# KitchenTimer.net
KiCad netlist of a schematic drawn in EAGLE
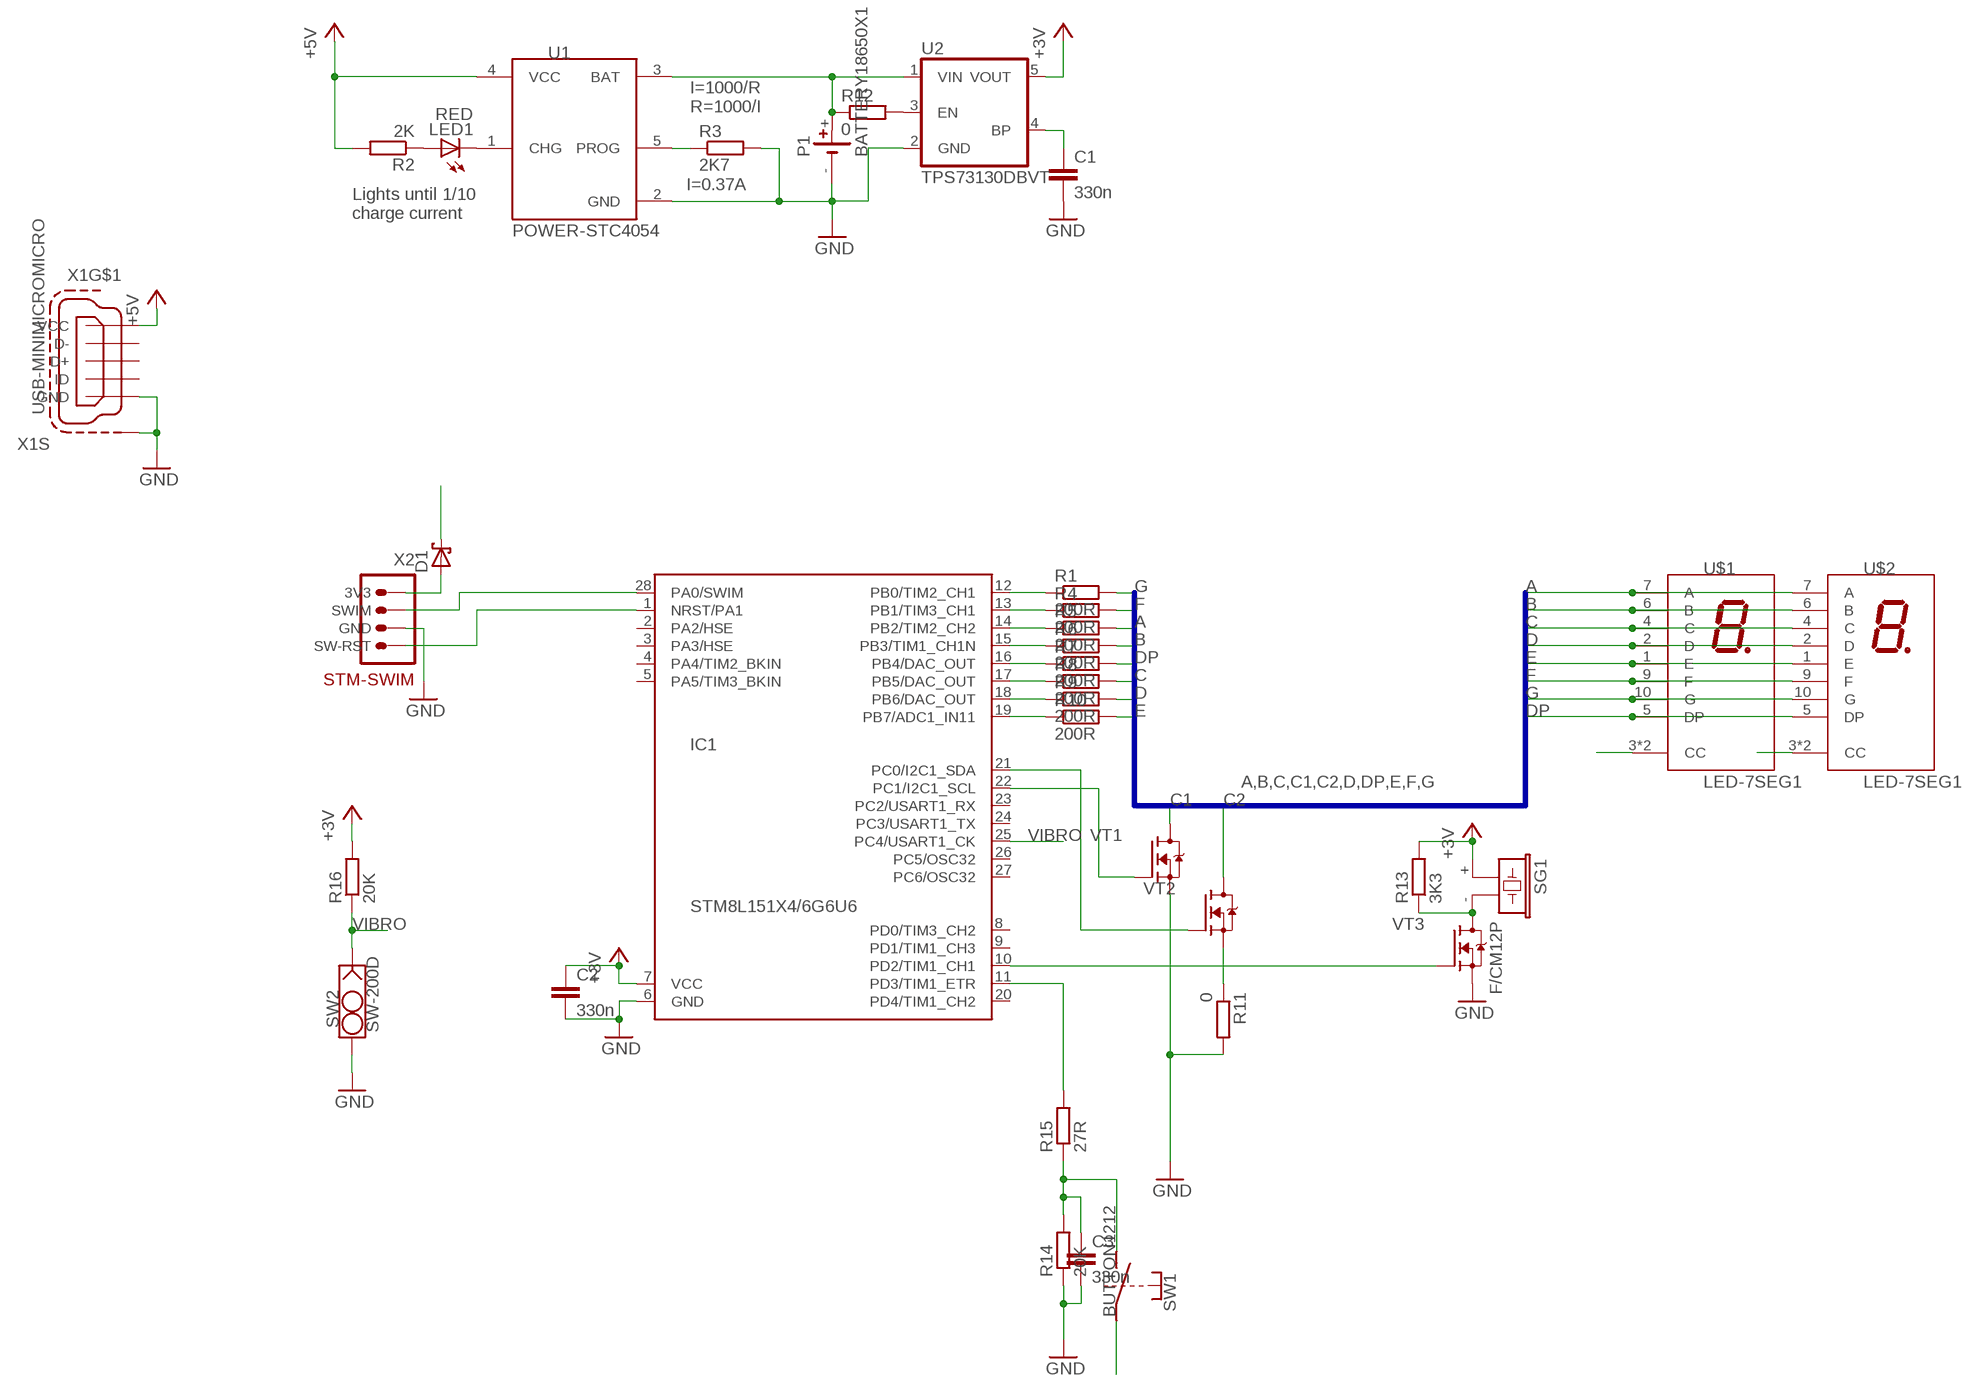
[diagram p0: schematic, sheet 1]

(export (version "E")
  (design (tool "Eeschema 10.0.6"))
  (components
    (comp (ref "C1")
      (value "330n")
      (footprint "eagle-import:CAP1206")
      (libsource (lib "eagle-import") (part "CAP_1206"))
    )
    (comp (ref "C2")
      (value "330n")
      (footprint "eagle-import:CAP1206")
      (libsource (lib "eagle-import") (part "CAP_1206"))
    )
    (comp (ref "C3")
      (value "330n")
      (footprint "eagle-import:CAP1206")
      (libsource (lib "eagle-import") (part "CAP_1206"))
    )
    (comp (ref "D1")
      (value "DIODE-SH_SOD523")
      (footprint "eagle-import:SODFL1608X65")
      (libsource (lib "eagle-import") (part "DIODE-SH_SOD523"))
    )
    (comp (ref "IC1")
      (value "STM8L151X4/6G6U6")
      (footprint "eagle-import:QFN28")
      (libsource (lib "eagle-import") (part "STM8L151X4/6G6U6"))
    )
    (comp (ref "LED1")
      (value "RED")
      (footprint "eagle-import:LED1206")
      (libsource (lib "eagle-import") (part "LED_1206"))
    )
    (comp (ref "P1")
      (value "BATTERY18650X1")
      (footprint "eagle-import:18650X1_HOLDER")
      (libsource (lib "eagle-import") (part "BATTERY18650X1"))
    )
    (comp (ref "R1")
      (value "200R")
      (footprint "eagle-import:RESC2012X50")
      (libsource (lib "eagle-import") (part "R_R0805"))
    )
    (comp (ref "R2")
      (value "2K")
      (footprint "eagle-import:RESC2012X50")
      (libsource (lib "eagle-import") (part "R_R0805"))
    )
    (comp (ref "R3")
      (value "2K7")
      (footprint "eagle-import:RESC2012X50")
      (libsource (lib "eagle-import") (part "R_R0805"))
    )
    (comp (ref "R4")
      (value "200R")
      (footprint "eagle-import:RESC2012X50")
      (libsource (lib "eagle-import") (part "R_R0805"))
    )
    (comp (ref "R5")
      (value "200R")
      (footprint "eagle-import:RESC2012X50")
      (libsource (lib "eagle-import") (part "R_R0805"))
    )
    (comp (ref "R6")
      (value "200R")
      (footprint "eagle-import:RESC2012X50")
      (libsource (lib "eagle-import") (part "R_R0805"))
    )
    (comp (ref "R7")
      (value "200R")
      (footprint "eagle-import:RESC2012X50")
      (libsource (lib "eagle-import") (part "R_R0805"))
    )
    (comp (ref "R8")
      (value "200R")
      (footprint "eagle-import:RESC2012X50")
      (libsource (lib "eagle-import") (part "R_R0805"))
    )
    (comp (ref "R9")
      (value "200R")
      (footprint "eagle-import:RESC2012X50")
      (libsource (lib "eagle-import") (part "R_R0805"))
    )
    (comp (ref "R10")
      (value "200R")
      (footprint "eagle-import:RESC2012X50")
      (libsource (lib "eagle-import") (part "R_R0805"))
    )
    (comp (ref "R11")
      (value "0")
      (footprint "eagle-import:RESC2012X50")
      (libsource (lib "eagle-import") (part "R_R0805"))
    )
    (comp (ref "R12")
      (value "0")
      (footprint "eagle-import:RESC2012X50")
      (libsource (lib "eagle-import") (part "R_R0805"))
    )
    (comp (ref "R13")
      (value "3K3")
      (footprint "eagle-import:RESC3216X60")
      (libsource (lib "eagle-import") (part "R_R1206"))
    )
    (comp (ref "R14")
      (value "20K")
      (footprint "eagle-import:RESC3216X60")
      (libsource (lib "eagle-import") (part "R_R1206"))
    )
    (comp (ref "R15")
      (value "27R")
      (footprint "eagle-import:RESC3216X60")
      (libsource (lib "eagle-import") (part "R_R1206"))
    )
    (comp (ref "R16")
      (value "20K")
      (footprint "eagle-import:RESC3216X60")
      (libsource (lib "eagle-import") (part "R_R1206"))
    )
    (comp (ref "SG1")
      (value "F/CM12P")
      (footprint "eagle-import:F_CM12P")
      (libsource (lib "eagle-import") (part "F/CM12P"))
    )
    (comp (ref "SW1")
      (value "BUTTON1212")
      (footprint "eagle-import:B3F-40XX")
      (libsource (lib "eagle-import") (part "BUTTON1212"))
    )
    (comp (ref "SW2")
      (value "SW-200D")
      (footprint "eagle-import:SW-200D")
      (libsource (lib "eagle-import") (part "SW-200D"))
    )
    (comp (ref "U$1")
      (value "LED-7SEG1")
      (footprint "eagle-import:LED-7SEG1")
      (libsource (lib "eagle-import") (part "LED-7SEG1"))
    )
    (comp (ref "U$2")
      (value "LED-7SEG1")
      (footprint "eagle-import:LED-7SEG1")
      (libsource (lib "eagle-import") (part "LED-7SEG1"))
    )
    (comp (ref "U1")
      (value "POWER-STC4054")
      (footprint "eagle-import:SOT95P280X145-5")
      (libsource (lib "eagle-import") (part "POWER-STC4054"))
    )
    (comp (ref "U2")
      (value "TPS73130DBVT")
      (footprint "eagle-import:SOT95P280X145-5")
      (libsource (lib "eagle-import") (part "VREG-LD2985"))
    )
    (comp (ref "VT1")
      (value "FET-NSOT-23")
      (footprint "eagle-import:SOT95P240X115-3")
      (libsource (lib "eagle-import") (part "FET-NSOT-23"))
    )
    (comp (ref "VT2")
      (value "FET-NSOT-23")
      (footprint "eagle-import:SOT95P240X115-3")
      (libsource (lib "eagle-import") (part "FET-NSOT-23"))
    )
    (comp (ref "VT3")
      (value "FET-NSOT-23")
      (footprint "eagle-import:SOT95P240X115-3")
      (libsource (lib "eagle-import") (part "FET-NSOT-23"))
    )
    (comp (ref "X1")
      (value "USB-MINIMICROMICRO")
      (footprint "eagle-import:USB-B-MICRO-SMD")
      (libsource (lib "eagle-import") (part "USB-MINIMICROMICRO"))
    )
    (comp (ref "X2")
      (value "STM-SWIMPOGOPADS")
      (footprint "eagle-import:SWIM-PADS-1.27")
      (libsource (lib "eagle-import") (part "STM-SWIMPOGOPADS"))
    )
  )
  (nets
    (net (code "1") (name "+3V") (class "Default")
      (node (ref "C2") (pin "1") (pinfunction "1_1") (pintype "passive"))
      (node (ref "D1") (pin "1") (pinfunction "C_1") (pintype "passive"))
      (node (ref "IC1") (pin "7") (pinfunction "VCC_7") (pintype "power_in"))
      (node (ref "R13") (pin "2") (pinfunction "2_2") (pintype "passive"))
      (node (ref "R16") (pin "2") (pinfunction "2_2") (pintype "passive"))
      (node (ref "SG1") (pin "+") (pinfunction "1_+") (pintype "passive"))
      (node (ref "SW1") (pin "1") (pinfunction "1_1") (pintype "passive"))
      (node (ref "SW1") (pin "2") (pinfunction "1_2") (pintype "passive"))
      (node (ref "U2") (pin "5") (pinfunction "VOUT_5") (pintype "passive"))
    )
    (net (code "2") (name "+5V") (class "Default")
      (node (ref "R2") (pin "2") (pinfunction "2_2") (pintype "passive"))
      (node (ref "U1") (pin "4") (pinfunction "VCC_4") (pintype "power_in"))
      (node (ref "X1") (pin "VBUS") (pinfunction "VCC_VBUS") (pintype "passive"))
    )
    (net (code "3") (name "/A") (class "Default")
      (node (ref "R5") (pin "2") (pinfunction "2_2") (pintype "passive"))
      (node (ref "U$1") (pin "7") (pinfunction "A_7") (pintype "bidirectional"))
      (node (ref "U$2") (pin "7") (pinfunction "A_7") (pintype "bidirectional"))
    )
    (net (code "4") (name "/B") (class "Default")
      (node (ref "R6") (pin "2") (pinfunction "2_2") (pintype "passive"))
      (node (ref "U$1") (pin "6") (pinfunction "B_6") (pintype "bidirectional"))
      (node (ref "U$2") (pin "6") (pinfunction "B_6") (pintype "bidirectional"))
    )
    (net (code "5") (name "/C") (class "Default")
      (node (ref "R8") (pin "2") (pinfunction "2_2") (pintype "passive"))
      (node (ref "U$1") (pin "4") (pinfunction "C_4") (pintype "bidirectional"))
      (node (ref "U$2") (pin "4") (pinfunction "C_4") (pintype "bidirectional"))
    )
    (net (code "6") (name "/C1") (class "Default")
      (node (ref "U$1") (pin "3") (pinfunction "CC_3") (pintype "bidirectional"))
      (node (ref "U$1") (pin "8") (pinfunction "CC_8") (pintype "bidirectional"))
      (node (ref "VT1") (pin "3") (pinfunction "D_3") (pintype "passive"))
    )
    (net (code "7") (name "/C2") (class "Default")
      (node (ref "U$2") (pin "3") (pinfunction "CC_3") (pintype "bidirectional"))
      (node (ref "U$2") (pin "8") (pinfunction "CC_8") (pintype "bidirectional"))
      (node (ref "VT2") (pin "3") (pinfunction "D_3") (pintype "passive"))
    )
    (net (code "8") (name "/D") (class "Default")
      (node (ref "R9") (pin "2") (pinfunction "2_2") (pintype "passive"))
      (node (ref "U$1") (pin "2") (pinfunction "D_2") (pintype "bidirectional"))
      (node (ref "U$2") (pin "2") (pinfunction "D_2") (pintype "bidirectional"))
    )
    (net (code "9") (name "/DP") (class "Default")
      (node (ref "R7") (pin "2") (pinfunction "2_2") (pintype "passive"))
      (node (ref "U$1") (pin "5") (pinfunction "DP_5") (pintype "bidirectional"))
      (node (ref "U$2") (pin "5") (pinfunction "DP_5") (pintype "bidirectional"))
    )
    (net (code "10") (name "/E") (class "Default")
      (node (ref "R10") (pin "2") (pinfunction "2_2") (pintype "passive"))
      (node (ref "U$1") (pin "1") (pinfunction "E_1") (pintype "bidirectional"))
      (node (ref "U$2") (pin "1") (pinfunction "E_1") (pintype "bidirectional"))
    )
    (net (code "11") (name "/F") (class "Default")
      (node (ref "R4") (pin "2") (pinfunction "2_2") (pintype "passive"))
      (node (ref "U$1") (pin "9") (pinfunction "F_9") (pintype "bidirectional"))
      (node (ref "U$2") (pin "9") (pinfunction "F_9") (pintype "bidirectional"))
    )
    (net (code "12") (name "/G") (class "Default")
      (node (ref "R1") (pin "2") (pinfunction "2_2") (pintype "passive"))
      (node (ref "U$1") (pin "10") (pinfunction "G_10") (pintype "bidirectional"))
      (node (ref "U$2") (pin "10") (pinfunction "G_10") (pintype "bidirectional"))
    )
    (net (code "13") (name "/VIBRO") (class "Default")
      (node (ref "IC1") (pin "25") (pinfunction "PC4/USART1_CK_25") (pintype "bidirectional"))
      (node (ref "R16") (pin "1") (pinfunction "1_1") (pintype "passive"))
      (node (ref "SW2") (pin "G") (pinfunction "G_G") (pintype "bidirectional"))
    )
    (net (code "14") (name "GND") (class "Default")
      (node (ref "C1") (pin "2") (pinfunction "2_2") (pintype "passive"))
      (node (ref "C2") (pin "2") (pinfunction "2_2") (pintype "passive"))
      (node (ref "C3") (pin "2") (pinfunction "2_2") (pintype "passive"))
      (node (ref "IC1") (pin "6") (pinfunction "GND_6") (pintype "power_in"))
      (node (ref "P1") (pin "-") (pinfunction "-_-") (pintype "passive"))
      (node (ref "R11") (pin "2") (pinfunction "2_2") (pintype "passive"))
      (node (ref "R14") (pin "1") (pinfunction "1_1") (pintype "passive"))
      (node (ref "R3") (pin "2") (pinfunction "2_2") (pintype "passive"))
      (node (ref "SW2") (pin "S") (pinfunction "S_S") (pintype "bidirectional"))
      (node (ref "U1") (pin "2") (pinfunction "GND_2") (pintype "power_in"))
      (node (ref "U2") (pin "2") (pinfunction "GND_2") (pintype "passive"))
      (node (ref "VT1") (pin "2") (pinfunction "S_2") (pintype "passive"))
      (node (ref "VT3") (pin "2") (pinfunction "S_2") (pintype "passive"))
      (node (ref "X1") (pin "GND") (pinfunction "GND_GND") (pintype "passive"))
      (node (ref "X1") (pin "SHIELD1") (pinfunction "S1_SHIELD1") (pintype "passive"))
      (node (ref "X1") (pin "SHIELD2") (pinfunction "S1_SHIELD2") (pintype "passive"))
      (node (ref "X1") (pin "SHIELD3") (pinfunction "S1_SHIELD3") (pintype "passive"))
      (node (ref "X2") (pin "P$3") (pinfunction "GND_P$3") (pintype "passive"))
    )
    (net (code "15") (name "Net-(C3-Pad1)") (class "Default")
      (node (ref "C3") (pin "1") (pinfunction "1_1") (pintype "passive"))
      (node (ref "R14") (pin "2") (pinfunction "2_2") (pintype "passive"))
      (node (ref "R15") (pin "1") (pinfunction "1_1") (pintype "passive"))
      (node (ref "SW1") (pin "3") (pinfunction "2_3") (pintype "passive"))
      (node (ref "SW1") (pin "4") (pinfunction "2_4") (pintype "passive"))
    )
    (net (code "16") (name "Net-(D1-A)") (class "Default")
      (node (ref "D1") (pin "2") (pinfunction "A_2") (pintype "passive"))
      (node (ref "X2") (pin "P$1") (pinfunction "3V3_P$1") (pintype "passive"))
    )
    (net (code "17") (name "Net-(IC1-NRST{slash}PA1)") (class "Default")
      (node (ref "IC1") (pin "1") (pinfunction "NRST/PA1_1") (pintype "bidirectional"))
      (node (ref "X2") (pin "P$4") (pinfunction "SW-RST_P$4") (pintype "passive"))
    )
    (net (code "18") (name "Net-(IC1-PA0{slash}SWIM)") (class "Default")
      (node (ref "IC1") (pin "28") (pinfunction "PA0/SWIM_28") (pintype "bidirectional"))
      (node (ref "X2") (pin "P$2") (pinfunction "SWIM_P$2") (pintype "passive"))
    )
    (net (code "19") (name "Net-(IC1-PB0{slash}TIM2_CH1)") (class "Default")
      (node (ref "IC1") (pin "12") (pinfunction "PB0/TIM2_CH1_12") (pintype "bidirectional"))
      (node (ref "R1") (pin "1") (pinfunction "1_1") (pintype "passive"))
    )
    (net (code "20") (name "Net-(IC1-PB1{slash}TIM3_CH1)") (class "Default")
      (node (ref "IC1") (pin "13") (pinfunction "PB1/TIM3_CH1_13") (pintype "bidirectional"))
      (node (ref "R4") (pin "1") (pinfunction "1_1") (pintype "passive"))
    )
    (net (code "21") (name "Net-(IC1-PB2{slash}TIM2_CH2)") (class "Default")
      (node (ref "IC1") (pin "14") (pinfunction "PB2/TIM2_CH2_14") (pintype "bidirectional"))
      (node (ref "R5") (pin "1") (pinfunction "1_1") (pintype "passive"))
    )
    (net (code "22") (name "Net-(IC1-PB3{slash}TIM1_CH1N)") (class "Default")
      (node (ref "IC1") (pin "15") (pinfunction "PB3/TIM1_CH1N_15") (pintype "bidirectional"))
      (node (ref "R6") (pin "1") (pinfunction "1_1") (pintype "passive"))
    )
    (net (code "23") (name "Net-(IC1-PB4{slash}DAC_OUT)") (class "Default")
      (node (ref "IC1") (pin "16") (pinfunction "PB4/DAC_OUT_16") (pintype "bidirectional"))
      (node (ref "R7") (pin "1") (pinfunction "1_1") (pintype "passive"))
    )
    (net (code "24") (name "Net-(IC1-PB5{slash}DAC_OUT)") (class "Default")
      (node (ref "IC1") (pin "17") (pinfunction "PB5/DAC_OUT_17") (pintype "bidirectional"))
      (node (ref "R8") (pin "1") (pinfunction "1_1") (pintype "passive"))
    )
    (net (code "25") (name "Net-(IC1-PB6{slash}DAC_OUT)") (class "Default")
      (node (ref "IC1") (pin "18") (pinfunction "PB6/DAC_OUT_18") (pintype "bidirectional"))
      (node (ref "R9") (pin "1") (pinfunction "1_1") (pintype "passive"))
    )
    (net (code "26") (name "Net-(IC1-PB7{slash}ADC1_IN11)") (class "Default")
      (node (ref "IC1") (pin "19") (pinfunction "PB7/ADC1_IN11_19") (pintype "bidirectional"))
      (node (ref "R10") (pin "1") (pinfunction "1_1") (pintype "passive"))
    )
    (net (code "27") (name "Net-(IC1-PC0{slash}I2C1_SDA)") (class "Default")
      (node (ref "IC1") (pin "21") (pinfunction "PC0/I2C1_SDA_21") (pintype "bidirectional"))
      (node (ref "VT2") (pin "1") (pinfunction "G_1") (pintype "passive"))
    )
    (net (code "28") (name "Net-(IC1-PC1{slash}I2C1_SCL)") (class "Default")
      (node (ref "IC1") (pin "22") (pinfunction "PC1/I2C1_SCL_22") (pintype "bidirectional"))
      (node (ref "VT1") (pin "1") (pinfunction "G_1") (pintype "passive"))
    )
    (net (code "29") (name "Net-(IC1-PD2{slash}TIM1_CH1)") (class "Default")
      (node (ref "IC1") (pin "10") (pinfunction "PD2/TIM1_CH1_10") (pintype "bidirectional"))
      (node (ref "VT3") (pin "1") (pinfunction "G_1") (pintype "passive"))
    )
    (net (code "30") (name "Net-(IC1-PD3{slash}TIM1_ETR)") (class "Default")
      (node (ref "IC1") (pin "11") (pinfunction "PD3/TIM1_ETR_11") (pintype "bidirectional"))
      (node (ref "R15") (pin "2") (pinfunction "2_2") (pintype "passive"))
    )
    (net (code "31") (name "Net-(LED1-PadA)") (class "Default")
      (node (ref "LED1") (pin "A") (pinfunction "A_A") (pintype "passive"))
      (node (ref "R2") (pin "1") (pinfunction "1_1") (pintype "passive"))
    )
    (net (code "32") (name "Net-(SG1-2)") (class "Default")
      (node (ref "R13") (pin "1") (pinfunction "1_1") (pintype "passive"))
      (node (ref "SG1") (pin "-") (pinfunction "2_-") (pintype "passive"))
      (node (ref "VT3") (pin "3") (pinfunction "D_3") (pintype "passive"))
    )
    (net (code "33") (name "Net-(U1-BAT)") (class "Default")
      (node (ref "P1") (pin "+") (pinfunction "+_+") (pintype "passive"))
      (node (ref "R12") (pin "1") (pinfunction "1_1") (pintype "passive"))
      (node (ref "U1") (pin "3") (pinfunction "BAT_3") (pintype "bidirectional"))
      (node (ref "U2") (pin "1") (pinfunction "VIN_1") (pintype "input"))
    )
    (net (code "34") (name "Net-(U1-CHG)") (class "Default")
      (node (ref "LED1") (pin "C") (pinfunction "C_C") (pintype "passive"))
      (node (ref "U1") (pin "1") (pinfunction "CHG_1") (pintype "output"))
    )
    (net (code "35") (name "Net-(U1-PROG)") (class "Default")
      (node (ref "R3") (pin "1") (pinfunction "1_1") (pintype "passive"))
      (node (ref "U1") (pin "5") (pinfunction "PROG_5") (pintype "bidirectional"))
    )
    (net (code "36") (name "Net-(U2-BP)") (class "Default")
      (node (ref "C1") (pin "1") (pinfunction "1_1") (pintype "passive"))
      (node (ref "U2") (pin "4") (pinfunction "BP_4") (pintype "input"))
    )
    (net (code "37") (name "Net-(U2-EN)") (class "Default")
      (node (ref "R12") (pin "2") (pinfunction "2_2") (pintype "passive"))
      (node (ref "U2") (pin "3") (pinfunction "EN_3") (pintype "input"))
    )
    (net (code "38") (name "Net-(VT2-S)") (class "Default")
      (node (ref "R11") (pin "1") (pinfunction "1_1") (pintype "passive"))
      (node (ref "VT2") (pin "2") (pinfunction "S_2") (pintype "passive"))
    )
    (net (code "39") (name "unconnected-(IC1-PA2{slash}HSE-Pad2)") (class "Default")
      (node (ref "IC1") (pin "2") (pinfunction "PA2/HSE_2") (pintype "bidirectional"))
    )
    (net (code "40") (name "unconnected-(IC1-PA3{slash}HSE-Pad3)") (class "Default")
      (node (ref "IC1") (pin "3") (pinfunction "PA3/HSE_3") (pintype "bidirectional"))
    )
    (net (code "41") (name "unconnected-(IC1-PA4{slash}TIM2_BKIN-Pad4)") (class "Default")
      (node (ref "IC1") (pin "4") (pinfunction "PA4/TIM2_BKIN_4") (pintype "bidirectional"))
    )
    (net (code "42") (name "unconnected-(IC1-PA5{slash}TIM3_BKIN-Pad5)") (class "Default")
      (node (ref "IC1") (pin "5") (pinfunction "PA5/TIM3_BKIN_5") (pintype "bidirectional"))
    )
    (net (code "43") (name "unconnected-(IC1-PC2{slash}USART1_RX-Pad23)") (class "Default")
      (node (ref "IC1") (pin "23") (pinfunction "PC2/USART1_RX_23") (pintype "bidirectional"))
    )
    (net (code "44") (name "unconnected-(IC1-PC3{slash}USART1_TX-Pad24)") (class "Default")
      (node (ref "IC1") (pin "24") (pinfunction "PC3/USART1_TX_24") (pintype "bidirectional"))
    )
    (net (code "45") (name "unconnected-(IC1-PC5{slash}OSC32-Pad26)") (class "Default")
      (node (ref "IC1") (pin "26") (pinfunction "PC5/OSC32_26") (pintype "bidirectional"))
    )
    (net (code "46") (name "unconnected-(IC1-PC6{slash}OSC32-Pad27)") (class "Default")
      (node (ref "IC1") (pin "27") (pinfunction "PC6/OSC32_27") (pintype "bidirectional"))
    )
    (net (code "47") (name "unconnected-(IC1-PD0{slash}TIM3_CH2-Pad8)") (class "Default")
      (node (ref "IC1") (pin "8") (pinfunction "PD0/TIM3_CH2_8") (pintype "bidirectional"))
    )
    (net (code "48") (name "unconnected-(IC1-PD1{slash}TIM1_CH3-Pad9)") (class "Default")
      (node (ref "IC1") (pin "9") (pinfunction "PD1/TIM1_CH3_9") (pintype "bidirectional"))
    )
    (net (code "49") (name "unconnected-(IC1-PD4{slash}TIM1_CH2-Pad20)") (class "Default")
      (node (ref "IC1") (pin "20") (pinfunction "PD4/TIM1_CH2_20") (pintype "bidirectional"))
    )
    (net (code "50") (name "unconnected-(X1-PadD+)") (class "Default")
      (node (ref "X1") (pin "D+") (pinfunction "D+_D+") (pintype "passive"))
    )
    (net (code "51") (name "unconnected-(X1-PadD-)") (class "Default")
      (node (ref "X1") (pin "D-") (pinfunction "D-_D-") (pintype "passive"))
    )
    (net (code "52") (name "unconnected-(X1-PadID)") (class "Default")
      (node (ref "X1") (pin "ID") (pinfunction "ID_ID") (pintype "passive"))
    )
  )
)
